# 03_-_Inter-connects.net
KiCad netlist of a schematic drawn in Altium Designer
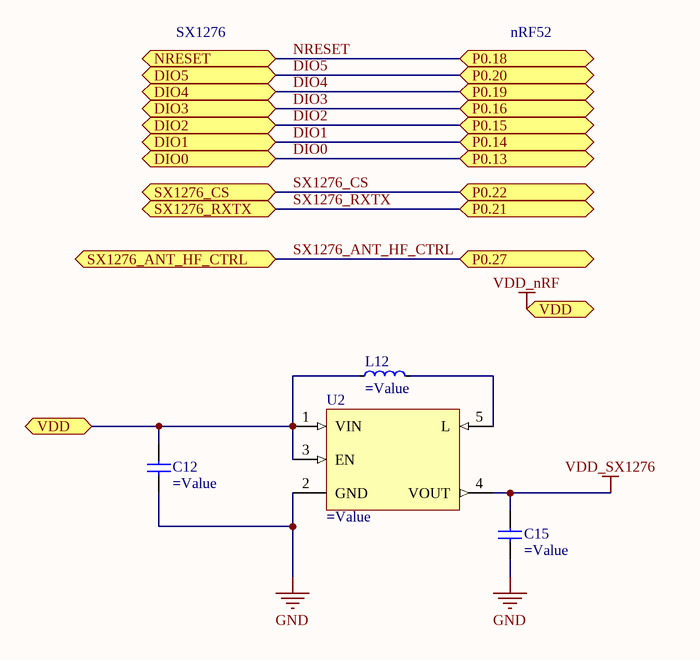
[diagram p0: [03] - Inter-connects.SchDoc]

(export (version "E")
  (design (tool "Eeschema 10.0.6"))
  (components
    (comp (ref "C12")
      (value "~")
      (footprint "CAPC1005X04L")
      (description "CAP CER 10UF 6.3V X5R 0402")
      (fields
        (field (name "MANUFACTURER") "Murata Electronics North America")
        (field (name "MANUFACTURER PART NUMBER") "GRM155R60J106ME15D")
      )
      (libsource (lib "Skunkworks Library") (part "GRM155R60J106ME15D"))
    )
    (comp (ref "C15")
      (value "~")
      (footprint "CAPC1005X04L")
      (description "CAP CER 10UF 6.3V X5R 0402")
      (fields
        (field (name "MANUFACTURER") "Murata Electronics North America")
        (field (name "MANUFACTURER PART NUMBER") "GRM155R60J106ME15D")
      )
      (libsource (lib "Skunkworks Library") (part "GRM155R60J106ME15D"))
    )
    (comp (ref "L12")
      (value "~")
      (footprint "INDC1608X06L")
      (description "FIXED IND 4.7UH 350MA 500 MOHM")
      (fields
        (field (name "MANUFACTURER") "TDK Corporation")
        (field (name "MANUFACTURER PART NUMBER") "MLZ1608M4R7WT000")
      )
      (libsource (lib "Skunkworks Library") (part "MLZ1608M4R7WT000"))
    )
    (comp (ref "U2")
      (value "~")
      (footprint "SOT95P280X145-5L")
      (description "IC REG BST 3.3V 0.2A SYNC SOT23")
      (fields
        (field (name "MANUFACTURER") "Texas Instruments")
        (field (name "MANUFACTURER PART NUMBER") "TPS61097A-33DBVR")
      )
      (libsource (lib "Skunkworks Library") (part "TPS61097A-33DBVR"))
    )
  )
  (nets
    (net (code "11") (name "GND") (class "Default")
      (node (ref "C12") (pin "1") (pinfunction "1_1") (pintype "passive"))
      (node (ref "C15") (pin "1") (pinfunction "1_1") (pintype "passive"))
      (node (ref "U2") (pin "2") (pinfunction "GND_2") (pintype "passive"))
    )
    (net (code "12") (name "Net-(U2-L)") (class "Default")
      (node (ref "L12") (pin "2") (pinfunction "2_2") (pintype "passive"))
      (node (ref "U2") (pin "5") (pinfunction "L_5") (pintype "input"))
    )
    (net (code "13") (name "VDD_SX1276") (class "Default")
      (node (ref "C15") (pin "2") (pinfunction "2_2") (pintype "passive"))
      (node (ref "U2") (pin "4") (pinfunction "VOUT_4") (pintype "output"))
    )
    (net (code "14") (name "VDD_nRF") (class "Default")
      (node (ref "C12") (pin "2") (pinfunction "2_2") (pintype "passive"))
      (node (ref "L12") (pin "1") (pinfunction "1_1") (pintype "passive"))
      (node (ref "U2") (pin "1") (pinfunction "VIN_1") (pintype "input"))
      (node (ref "U2") (pin "3") (pinfunction "EN_3") (pintype "input"))
    )
  )
)
